# DSP.net
KiCad netlist of a schematic drawn in Altium Designer
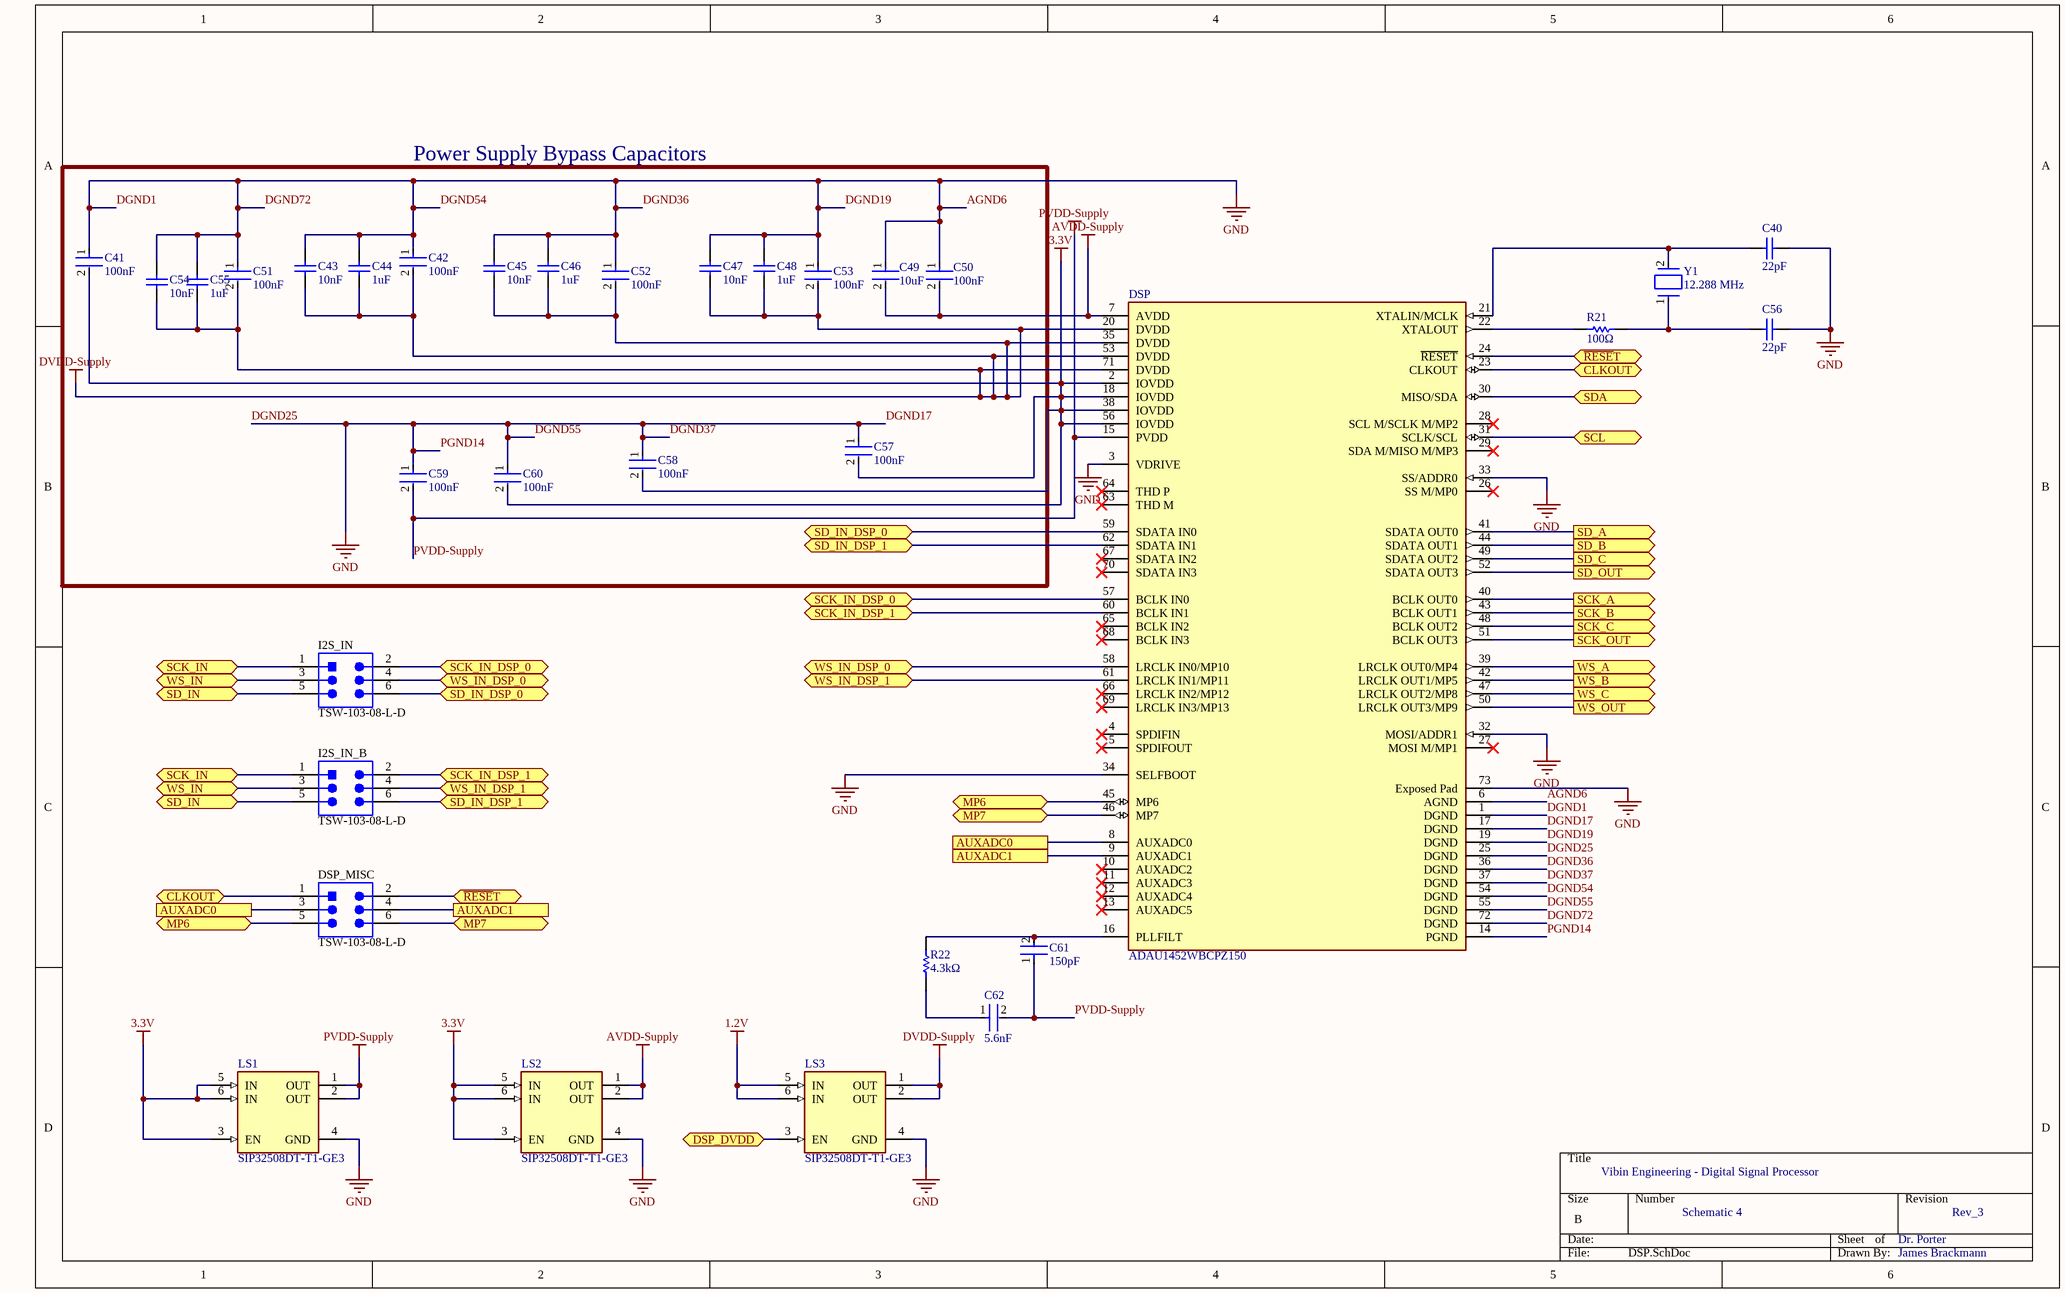
[diagram p0: DSP.SchDoc]

(export (version "E")
  (design (tool "Eeschema 10.0.6"))
  (components
    (comp (ref "C40")
      (value "22pF")
      (footprint "CAPC1608X90X35ML10T15")
      (fields (field (name "MANUFACTURER") "Murata"))
      (libsource (lib "Altium Content Vault") (part "CAP-NP-2"))
    )
    (comp (ref "C41")
      (value "100nF")
      (footprint "FP-C0402-BB-MFG")
      (description "CAP CER 0.1UF 10V X5R 0402             C0402C104K8PACTU")
      (fields (field (name "MANUFACTURER") "Kemet") (field (name "TOLERANCE") "0.1"))
      (libsource (lib "Altium Content Vault") (part "b4654b650e69147ec39a6b967a45e02"))
    )
    (comp (ref "C42")
      (value "100nF")
      (footprint "FP-C0402-BB-MFG")
      (description "CAP CER 0.1UF 10V X5R 0402             C0402C104K8PACTU")
      (fields (field (name "MANUFACTURER") "Kemet") (field (name "TOLERANCE") "0.1"))
      (libsource (lib "Altium Content Vault") (part "b4654b650e69147ec39a6b967a45e02"))
    )
    (comp (ref "C43")
      (value "10nF")
      (footprint "CAPC1005X56X25NL10T15")
      (description "0402ZC103KAT2A")
      (fields (field (name "MANUFACTURER") "AVX Interconnect / Elco"))
      (libsource (lib "Altium Content Vault") (part "CAP"))
    )
    (comp (ref "C44")
      (value "1uF")
      (footprint "CAPC2013X145X50LL20T25")
      (description "C0805C105K4PACTU")
      (fields (field (name "MANUFACTURER") "Kemet"))
      (libsource (lib "Altium Content Vault") (part "CAP"))
    )
    (comp (ref "C45")
      (value "10nF")
      (footprint "CAPC1005X56X25NL10T15")
      (description "0402ZC103KAT2A")
      (fields (field (name "MANUFACTURER") "AVX Interconnect / Elco"))
      (libsource (lib "Altium Content Vault") (part "CAP"))
    )
    (comp (ref "C46")
      (value "1uF")
      (footprint "CAPC2013X145X50LL20T25")
      (description "C0805C105K4PACTU")
      (fields (field (name "MANUFACTURER") "Kemet"))
      (libsource (lib "Altium Content Vault") (part "CAP"))
    )
    (comp (ref "C47")
      (value "10nF")
      (footprint "CAPC1005X56X25NL10T15")
      (description "0402ZC103KAT2A")
      (fields (field (name "MANUFACTURER") "AVX Interconnect / Elco"))
      (libsource (lib "Altium Content Vault") (part "CAP"))
    )
    (comp (ref "C48")
      (value "1uF")
      (footprint "CAPC2013X145X50LL20T25")
      (description "C0805C105K4PACTU")
      (fields (field (name "MANUFACTURER") "Kemet"))
      (libsource (lib "Altium Content Vault") (part "CAP"))
    )
    (comp (ref "C49")
      (value "10uF")
      (footprint "FP-GRM188-0_1-e0_2_0_55-IPC_A")
      (fields (field (name "VOLTAGE") "6.3V") (field (name "TOLERANCE") "20%"))
      (libsource (lib "Altium Content Vault") (part "02cd4be3c70576c341d710602a673aa"))
    )
    (comp (ref "C50")
      (value "100nF")
      (footprint "FP-C0402-BB-MFG")
      (description "CAP CER 0.1UF 10V X5R 0402             C0402C104K8PACTU")
      (fields (field (name "MANUFACTURER") "Kemet") (field (name "TOLERANCE") "0.1"))
      (libsource (lib "Altium Content Vault") (part "b4654b650e69147ec39a6b967a45e02"))
    )
    (comp (ref "C51")
      (value "100nF")
      (footprint "FP-C0402-BB-MFG")
      (description "CAP CER 0.1UF 10V X5R 0402             C0402C104K8PACTU")
      (fields (field (name "MANUFACTURER") "Kemet") (field (name "TOLERANCE") "0.1"))
      (libsource (lib "Altium Content Vault") (part "b4654b650e69147ec39a6b967a45e02"))
    )
    (comp (ref "C52")
      (value "100nF")
      (footprint "FP-C0402-BB-MFG")
      (description "CAP CER 0.1UF 10V X5R 0402             C0402C104K8PACTU")
      (fields (field (name "MANUFACTURER") "Kemet") (field (name "TOLERANCE") "0.1"))
      (libsource (lib "Altium Content Vault") (part "b4654b650e69147ec39a6b967a45e02"))
    )
    (comp (ref "C53")
      (value "100nF")
      (footprint "FP-C0402-BB-MFG")
      (description "CAP CER 0.1UF 10V X5R 0402             C0402C104K8PACTU")
      (fields (field (name "MANUFACTURER") "Kemet") (field (name "TOLERANCE") "0.1"))
      (libsource (lib "Altium Content Vault") (part "b4654b650e69147ec39a6b967a45e02"))
    )
    (comp (ref "C54")
      (value "10nF")
      (footprint "CAPC1005X56X25NL10T15")
      (description "0402ZC103KAT2A")
      (fields (field (name "MANUFACTURER") "AVX Interconnect / Elco"))
      (libsource (lib "Altium Content Vault") (part "CAP"))
    )
    (comp (ref "C55")
      (value "1uF")
      (footprint "CAPC2013X145X50LL20T25")
      (description "C0805C105K4PACTU")
      (fields (field (name "MANUFACTURER") "Kemet"))
      (libsource (lib "Altium Content Vault") (part "CAP"))
    )
    (comp (ref "C56")
      (value "22pF")
      (footprint "CAPC1608X90X35ML10T15")
      (fields (field (name "MANUFACTURER") "Murata"))
      (libsource (lib "Altium Content Vault") (part "CAP-NP-2"))
    )
    (comp (ref "C57")
      (value "100nF")
      (footprint "FP-C0402-BB-MFG")
      (description "CAP CER 0.1UF 10V X5R 0402             C0402C104K8PACTU")
      (fields (field (name "MANUFACTURER") "Kemet") (field (name "TOLERANCE") "0.1"))
      (libsource (lib "Altium Content Vault") (part "b4654b650e69147ec39a6b967a45e02"))
    )
    (comp (ref "C58")
      (value "100nF")
      (footprint "FP-C0402-BB-MFG")
      (description "CAP CER 0.1UF 10V X5R 0402             C0402C104K8PACTU")
      (fields (field (name "MANUFACTURER") "Kemet") (field (name "TOLERANCE") "0.1"))
      (libsource (lib "Altium Content Vault") (part "b4654b650e69147ec39a6b967a45e02"))
    )
    (comp (ref "C59")
      (value "100nF")
      (footprint "FP-C0402-BB-MFG")
      (description "CAP CER 0.1UF 10V X5R 0402             C0402C104K8PACTU")
      (fields (field (name "MANUFACTURER") "Kemet") (field (name "TOLERANCE") "0.1"))
      (libsource (lib "Altium Content Vault") (part "b4654b650e69147ec39a6b967a45e02"))
    )
    (comp (ref "C60")
      (value "100nF")
      (footprint "FP-C0402-BB-MFG")
      (description "CAP CER 0.1UF 10V X5R 0402             C0402C104K8PACTU")
      (fields (field (name "MANUFACTURER") "Kemet") (field (name "TOLERANCE") "0.1"))
      (libsource (lib "Altium Content Vault") (part "b4654b650e69147ec39a6b967a45e02"))
    )
    (comp (ref "C61")
      (value "150pF")
      (footprint "FP-0805-L_2_01_0_2-W_1_25-IPC_B")
      (description "General Purpose Ceramic Capacitor, 0805, 150pF, 5%, C0G, 30ppm/°C, 200V         08052A151JAT2A")
      (fields (field (name "TOLERANCE") "5%") (field (name "VOLTAGE") "200V"))
      (libsource (lib "Altium Content Vault") (part "02cd4be3c70576c341d710602a673aa"))
    )
    (comp (ref "C62")
      (value "5.6nF")
      (footprint "FP-CL10-IPC_A")
      (description "Cap Ceramic 5.6nF 50V X7R ±10% Pad SMD 0603 +125°C T/R            CL10B562KB8NNNC")
      (fields (field (name "VOLTAGE") "50V") (field (name "TOLERANCE") "10%"))
      (libsource (lib "Altium Content Vault") (part "b4654b650e69147ec39a6b967a45e02"))
    )
    (comp (ref "DSP")
      (value "ADAU1452WBCPZ150")
      (footprint "FP-CP-72-6-IPC_B")
      (description "150 MHZ 32BIT SIGMADSP AUDIO PRO")
      (fields (field (name "MANUFACTURER") "Analog Devices"))
      (libsource (lib "VibinTest1_1") (part "CMP-09089-000039-1"))
    )
    (comp (ref "DSP_MISC")
      (value "TSW-103-08-L-D")
      (footprint "SMTC-TSW-103-08-L-D_V")
      (fields (field (name "MANUFACTURER") "Samtec"))
      (libsource (lib "Altium Content Vault") (part "CN-2P-M-R6"))
    )
    (comp (ref "I2S_IN")
      (value "TSW-103-08-L-D")
      (footprint "SMTC-TSW-103-08-L-D_V")
      (fields (field (name "MANUFACTURER") "Samtec"))
      (libsource (lib "Altium Content Vault") (part "CN-2P-M-R6"))
    )
    (comp (ref "I2S_IN_B")
      (value "TSW-103-08-L-D")
      (footprint "SMTC-TSW-103-08-L-D_V")
      (fields (field (name "MANUFACTURER") "Samtec"))
      (libsource (lib "Altium Content Vault") (part "CN-2P-M-R6"))
    )
    (comp (ref "LS1")
      (value "SIP32508DT-T1-GE3")
      (footprint "FP-E13-1126-IPC_C")
      (description "IC PWR SWTCH N-CHAN 1:1 TSOT23-6")
      (fields
        (field (name "OCTOPART") "https://octopart.com/sip32508dt-t1-ge3-vishay-29622757")
        (field (name "MANUFACTURER") "Vishay")
      )
      (libsource (lib "Altium Content Vault") (part "141890209d49669e58eba095c1ea2ce"))
    )
    (comp (ref "LS2")
      (value "SIP32508DT-T1-GE3")
      (footprint "FP-E13-1126-IPC_C")
      (description "IC PWR SWTCH N-CHAN 1:1 TSOT23-6")
      (fields
        (field (name "OCTOPART") "https://octopart.com/sip32508dt-t1-ge3-vishay-29622757")
        (field (name "MANUFACTURER") "Vishay")
      )
      (libsource (lib "Altium Content Vault") (part "141890209d49669e58eba095c1ea2ce"))
    )
    (comp (ref "LS3")
      (value "SIP32508DT-T1-GE3")
      (footprint "FP-E13-1126-IPC_C")
      (description "IC PWR SWTCH N-CHAN 1:1 TSOT23-6")
      (fields
        (field (name "OCTOPART") "https://octopart.com/sip32508dt-t1-ge3-vishay-29622757")
        (field (name "MANUFACTURER") "Vishay")
      )
      (libsource (lib "Altium Content Vault") (part "141890209d49669e58eba095c1ea2ce"))
    )
    (comp (ref "R21")
      (value "100Ω")
      (footprint "RESC2013X60X40ML20T25")
      (description "ERA6AEB101V")
      (fields (field (name "MANUFACTURER") "Panasonic"))
      (libsource (lib "Altium Content Vault") (part "RES"))
    )
    (comp (ref "R22")
      (value "4.3kΩ")
      (footprint "RESC1005X40X25ML05T10")
      (description "RC0402FR-074K3L")
      (fields (field (name "MANUFACTURER") "Yageo / Phycomp"))
      (libsource (lib "Altium Content Vault") (part "RES"))
    )
    (comp (ref "Y1")
      (value "12.288 MHz")
      (footprint "FP-ABM3-MFG")
      (description "Crystal 12.288MHz ±20ppm 18pF SMD-2 5mm x 3.2mm           ABM3-12.288MHZ-D2Y-T")
      (fields (field (name "TOLERANCE") "20ppm"))
      (libsource (lib "Altium Content Vault") (part "c23a69dc6c9e2f18f2079038eb95dd1"))
    )
  )
  (nets
    (net (code "1") (name "/AUXADC0") (class "Default")
      (node (ref "DSP") (pin "8") (pinfunction "AUXADC0_8") (pintype "passive"))
      (node (ref "DSP_MISC") (pin "3") (pinfunction "3_3") (pintype "passive"))
    )
    (net (code "2") (name "/AUXADC1") (class "Default")
      (node (ref "DSP") (pin "9") (pinfunction "AUXADC1_9") (pintype "passive"))
      (node (ref "DSP_MISC") (pin "4") (pinfunction "4_4") (pintype "passive"))
    )
    (net (code "3") (name "/CLKOUT") (class "Default")
      (node (ref "DSP") (pin "23") (pinfunction "CLKOUT_23") (pintype "bidirectional"))
      (node (ref "DSP_MISC") (pin "1") (pinfunction "1_1") (pintype "passive"))
    )
    (net (code "4") (name "/DSP_DVDD") (class "Default")
      (node (ref "LS3") (pin "3") (pinfunction "EN_3") (pintype "input"))
    )
    (net (code "5") (name "/MP6") (class "Default")
      (node (ref "DSP") (pin "45") (pinfunction "MP6_45") (pintype "bidirectional"))
      (node (ref "DSP_MISC") (pin "5") (pinfunction "5_5") (pintype "passive"))
    )
    (net (code "6") (name "/MP7") (class "Default")
      (node (ref "DSP") (pin "46") (pinfunction "MP7_46") (pintype "bidirectional"))
      (node (ref "DSP_MISC") (pin "6") (pinfunction "6_6") (pintype "passive"))
    )
    (net (code "7") (name "/SCK_A") (class "Default")
      (node (ref "DSP") (pin "40") (pinfunction "BCLK_OUT0_40") (pintype "output"))
    )
    (net (code "8") (name "/SCK_B") (class "Default")
      (node (ref "DSP") (pin "43") (pinfunction "BCLK_OUT1_43") (pintype "output"))
    )
    (net (code "9") (name "/SCK_C") (class "Default")
      (node (ref "DSP") (pin "48") (pinfunction "BCLK_OUT2_48") (pintype "output"))
    )
    (net (code "10") (name "/SCK_IN") (class "Default")
      (node (ref "I2S_IN") (pin "1") (pinfunction "1_1") (pintype "passive"))
      (node (ref "I2S_IN_B") (pin "1") (pinfunction "1_1") (pintype "passive"))
    )
    (net (code "11") (name "/SCK_IN_DSP_0") (class "Default")
      (node (ref "DSP") (pin "57") (pinfunction "BCLK_IN0_57") (pintype "passive"))
      (node (ref "I2S_IN") (pin "2") (pinfunction "2_2") (pintype "passive"))
    )
    (net (code "12") (name "/SCK_IN_DSP_1") (class "Default")
      (node (ref "DSP") (pin "60") (pinfunction "BCLK_IN1_60") (pintype "passive"))
      (node (ref "I2S_IN_B") (pin "2") (pinfunction "2_2") (pintype "passive"))
    )
    (net (code "13") (name "/SCK_OUT") (class "Default")
      (node (ref "DSP") (pin "51") (pinfunction "BCLK_OUT3_51") (pintype "output"))
    )
    (net (code "14") (name "/SCL") (class "Default")
      (node (ref "DSP") (pin "31") (pinfunction "SCLK/SCL_31") (pintype "bidirectional"))
    )
    (net (code "15") (name "/SDA") (class "Default")
      (node (ref "DSP") (pin "30") (pinfunction "MISO/SDA_30") (pintype "bidirectional"))
    )
    (net (code "16") (name "/SD_A") (class "Default")
      (node (ref "DSP") (pin "41") (pinfunction "SDATA_OUT0_41") (pintype "output"))
    )
    (net (code "17") (name "/SD_B") (class "Default")
      (node (ref "DSP") (pin "44") (pinfunction "SDATA_OUT1_44") (pintype "output"))
    )
    (net (code "18") (name "/SD_C") (class "Default")
      (node (ref "DSP") (pin "49") (pinfunction "SDATA_OUT2_49") (pintype "output"))
    )
    (net (code "19") (name "/SD_IN") (class "Default")
      (node (ref "I2S_IN") (pin "5") (pinfunction "5_5") (pintype "passive"))
      (node (ref "I2S_IN_B") (pin "5") (pinfunction "5_5") (pintype "passive"))
    )
    (net (code "20") (name "/SD_IN_DSP_0") (class "Default")
      (node (ref "DSP") (pin "59") (pinfunction "SDATA_IN0_59") (pintype "passive"))
      (node (ref "I2S_IN") (pin "6") (pinfunction "6_6") (pintype "passive"))
    )
    (net (code "21") (name "/SD_IN_DSP_1") (class "Default")
      (node (ref "DSP") (pin "62") (pinfunction "SDATA_IN1_62") (pintype "passive"))
      (node (ref "I2S_IN_B") (pin "6") (pinfunction "6_6") (pintype "passive"))
    )
    (net (code "22") (name "/SD_OUT") (class "Default")
      (node (ref "DSP") (pin "52") (pinfunction "SDATA_OUT3_52") (pintype "output"))
    )
    (net (code "23") (name "/WS_A") (class "Default")
      (node (ref "DSP") (pin "39") (pinfunction "LRCLK_OUT0/MP4_39") (pintype "output"))
    )
    (net (code "24") (name "/WS_B") (class "Default")
      (node (ref "DSP") (pin "42") (pinfunction "LRCLK_OUT1/MP5_42") (pintype "output"))
    )
    (net (code "25") (name "/WS_C") (class "Default")
      (node (ref "DSP") (pin "47") (pinfunction "LRCLK_OUT2/MP8_47") (pintype "output"))
    )
    (net (code "26") (name "/WS_IN") (class "Default")
      (node (ref "I2S_IN") (pin "3") (pinfunction "3_3") (pintype "passive"))
      (node (ref "I2S_IN_B") (pin "3") (pinfunction "3_3") (pintype "passive"))
    )
    (net (code "27") (name "/WS_IN_DSP_0") (class "Default")
      (node (ref "DSP") (pin "58") (pinfunction "LRCLK_IN0/MP10_58") (pintype "passive"))
      (node (ref "I2S_IN") (pin "4") (pinfunction "4_4") (pintype "passive"))
    )
    (net (code "28") (name "/WS_IN_DSP_1") (class "Default")
      (node (ref "DSP") (pin "61") (pinfunction "LRCLK_IN1/MP11_61") (pintype "passive"))
      (node (ref "I2S_IN_B") (pin "4") (pinfunction "4_4") (pintype "passive"))
    )
    (net (code "29") (name "/WS_OUT") (class "Default")
      (node (ref "DSP") (pin "50") (pinfunction "LRCLK_OUT3/MP9_50") (pintype "output"))
    )
    (net (code "30") (name "/~{RESE}T") (class "Default")
      (node (ref "DSP") (pin "24") (pinfunction "~{RESET}_24") (pintype "input"))
      (node (ref "DSP_MISC") (pin "2") (pinfunction "2_2") (pintype "passive"))
    )
    (net (code "31") (name "1.2V") (class "Default")
      (node (ref "LS3") (pin "5") (pinfunction "IN_5") (pintype "input"))
      (node (ref "LS3") (pin "6") (pinfunction "IN_6") (pintype "input"))
    )
    (net (code "32") (name "3.3V") (class "Default")
      (node (ref "C41") (pin "2") (pinfunction "2_2") (pintype "passive"))
      (node (ref "C57") (pin "2") (pinfunction "2_2") (pintype "passive"))
      (node (ref "C58") (pin "2") (pinfunction "2_2") (pintype "passive"))
      (node (ref "C60") (pin "2") (pinfunction "2_2") (pintype "passive"))
      (node (ref "DSP") (pin "18") (pinfunction "IOVDD_18") (pintype "power_in"))
      (node (ref "DSP") (pin "2") (pinfunction "IOVDD_2") (pintype "power_in"))
      (node (ref "DSP") (pin "38") (pinfunction "IOVDD_38") (pintype "power_in"))
      (node (ref "DSP") (pin "56") (pinfunction "IOVDD_56") (pintype "power_in"))
      (node (ref "LS1") (pin "3") (pinfunction "EN_3") (pintype "input"))
      (node (ref "LS1") (pin "5") (pinfunction "IN_5") (pintype "input"))
      (node (ref "LS1") (pin "6") (pinfunction "IN_6") (pintype "input"))
      (node (ref "LS2") (pin "3") (pinfunction "EN_3") (pintype "input"))
      (node (ref "LS2") (pin "5") (pinfunction "IN_5") (pintype "input"))
      (node (ref "LS2") (pin "6") (pinfunction "IN_6") (pintype "input"))
    )
    (net (code "33") (name "AVDD-Supply") (class "Default")
      (node (ref "C49") (pin "2") (pinfunction "2_2") (pintype "passive"))
      (node (ref "C50") (pin "2") (pinfunction "2_2") (pintype "passive"))
      (node (ref "DSP") (pin "7") (pinfunction "AVDD_7") (pintype "power_in"))
      (node (ref "LS2") (pin "1") (pinfunction "OUT_1") (pintype "passive"))
      (node (ref "LS2") (pin "2") (pinfunction "OUT_2") (pintype "passive"))
    )
    (net (code "34") (name "DVDD-Supply") (class "Default")
      (node (ref "C42") (pin "2") (pinfunction "2_2") (pintype "passive"))
      (node (ref "C43") (pin "1") (pinfunction "1_1") (pintype "passive"))
      (node (ref "C44") (pin "1") (pinfunction "1_1") (pintype "passive"))
      (node (ref "C45") (pin "1") (pinfunction "1_1") (pintype "passive"))
      (node (ref "C46") (pin "1") (pinfunction "1_1") (pintype "passive"))
      (node (ref "C47") (pin "1") (pinfunction "1_1") (pintype "passive"))
      (node (ref "C48") (pin "1") (pinfunction "1_1") (pintype "passive"))
      (node (ref "C51") (pin "2") (pinfunction "2_2") (pintype "passive"))
      (node (ref "C52") (pin "2") (pinfunction "2_2") (pintype "passive"))
      (node (ref "C53") (pin "2") (pinfunction "2_2") (pintype "passive"))
      (node (ref "C54") (pin "1") (pinfunction "1_1") (pintype "passive"))
      (node (ref "C55") (pin "1") (pinfunction "1_1") (pintype "passive"))
      (node (ref "DSP") (pin "20") (pinfunction "DVDD_20") (pintype "power_in"))
      (node (ref "DSP") (pin "35") (pinfunction "DVDD_35") (pintype "power_in"))
      (node (ref "DSP") (pin "53") (pinfunction "DVDD_53") (pintype "power_in"))
      (node (ref "DSP") (pin "71") (pinfunction "DVDD_71") (pintype "power_in"))
      (node (ref "LS3") (pin "1") (pinfunction "OUT_1") (pintype "passive"))
      (node (ref "LS3") (pin "2") (pinfunction "OUT_2") (pintype "passive"))
    )
    (net (code "35") (name "GND") (class "Default")
      (node (ref "C40") (pin "2") (pinfunction "2_2") (pintype "passive"))
      (node (ref "C41") (pin "1") (pinfunction "1_1") (pintype "passive"))
      (node (ref "C42") (pin "1") (pinfunction "1_1") (pintype "passive"))
      (node (ref "C43") (pin "2") (pinfunction "2_2") (pintype "passive"))
      (node (ref "C44") (pin "2") (pinfunction "2_2") (pintype "passive"))
      (node (ref "C45") (pin "2") (pinfunction "2_2") (pintype "passive"))
      (node (ref "C46") (pin "2") (pinfunction "2_2") (pintype "passive"))
      (node (ref "C47") (pin "2") (pinfunction "2_2") (pintype "passive"))
      (node (ref "C48") (pin "2") (pinfunction "2_2") (pintype "passive"))
      (node (ref "C49") (pin "1") (pinfunction "1_1") (pintype "passive"))
      (node (ref "C50") (pin "1") (pinfunction "1_1") (pintype "passive"))
      (node (ref "C51") (pin "1") (pinfunction "1_1") (pintype "passive"))
      (node (ref "C52") (pin "1") (pinfunction "1_1") (pintype "passive"))
      (node (ref "C53") (pin "1") (pinfunction "1_1") (pintype "passive"))
      (node (ref "C54") (pin "2") (pinfunction "2_2") (pintype "passive"))
      (node (ref "C55") (pin "2") (pinfunction "2_2") (pintype "passive"))
      (node (ref "C56") (pin "2") (pinfunction "2_2") (pintype "passive"))
      (node (ref "C57") (pin "1") (pinfunction "1_1") (pintype "passive"))
      (node (ref "C58") (pin "1") (pinfunction "1_1") (pintype "passive"))
      (node (ref "C59") (pin "1") (pinfunction "1_1") (pintype "passive"))
      (node (ref "C60") (pin "1") (pinfunction "1_1") (pintype "passive"))
      (node (ref "DSP") (pin "1") (pinfunction "DGND_1") (pintype "power_in"))
      (node (ref "DSP") (pin "14") (pinfunction "PGND_14") (pintype "power_in"))
      (node (ref "DSP") (pin "17") (pinfunction "DGND_17") (pintype "power_in"))
      (node (ref "DSP") (pin "19") (pinfunction "DGND_19") (pintype "power_in"))
      (node (ref "DSP") (pin "25") (pinfunction "DGND_25") (pintype "power_in"))
      (node (ref "DSP") (pin "3") (pinfunction "VDRIVE_3") (pintype "passive"))
      (node (ref "DSP") (pin "32") (pinfunction "MOSI/ADDR1_32") (pintype "input"))
      (node (ref "DSP") (pin "33") (pinfunction "SS/ADDR0_33") (pintype "input"))
      (node (ref "DSP") (pin "34") (pinfunction "SELFBOOT_34") (pintype "passive"))
      (node (ref "DSP") (pin "36") (pinfunction "DGND_36") (pintype "power_in"))
      (node (ref "DSP") (pin "37") (pinfunction "DGND_37") (pintype "power_in"))
      (node (ref "DSP") (pin "54") (pinfunction "DGND_54") (pintype "power_in"))
      (node (ref "DSP") (pin "55") (pinfunction "DGND_55") (pintype "power_in"))
      (node (ref "DSP") (pin "6") (pinfunction "AGND_6") (pintype "power_in"))
      (node (ref "DSP") (pin "72") (pinfunction "DGND_72") (pintype "power_in"))
      (node (ref "DSP") (pin "73") (pinfunction "Exposed_Pad_73") (pintype "power_in"))
      (node (ref "LS1") (pin "4") (pinfunction "GND_4") (pintype "power_in"))
      (node (ref "LS2") (pin "4") (pinfunction "GND_4") (pintype "power_in"))
      (node (ref "LS3") (pin "4") (pinfunction "GND_4") (pintype "power_in"))
    )
    (net (code "36") (name "Net-(C56-Pad1)") (class "Default")
      (node (ref "C56") (pin "1") (pinfunction "1_1") (pintype "passive"))
      (node (ref "R21") (pin "2") (pinfunction "2_2") (pintype "passive"))
      (node (ref "Y1") (pin "1") (pinfunction "1_1") (pintype "passive"))
    )
    (net (code "37") (name "Net-(C62-Pad1)") (class "Default")
      (node (ref "C62") (pin "1") (pinfunction "1_1") (pintype "passive"))
      (node (ref "R22") (pin "1") (pinfunction "1_1") (pintype "passive"))
    )
    (net (code "38") (name "Net-(DSP-PLLFILT)") (class "Default")
      (node (ref "C61") (pin "2") (pinfunction "2_2") (pintype "passive"))
      (node (ref "DSP") (pin "16") (pinfunction "PLLFILT_16") (pintype "passive"))
      (node (ref "R22") (pin "2") (pinfunction "2_2") (pintype "passive"))
    )
    (net (code "39") (name "Net-(DSP-XTALIN{slash}MCLK)") (class "Default")
      (node (ref "C40") (pin "1") (pinfunction "1_1") (pintype "passive"))
      (node (ref "DSP") (pin "21") (pinfunction "XTALIN/MCLK_21") (pintype "input"))
      (node (ref "Y1") (pin "2") (pinfunction "2_2") (pintype "passive"))
    )
    (net (code "40") (name "Net-(DSP-XTALOUT)") (class "Default")
      (node (ref "DSP") (pin "22") (pinfunction "XTALOUT_22") (pintype "output"))
      (node (ref "R21") (pin "1") (pinfunction "1_1") (pintype "passive"))
    )
    (net (code "41") (name "PVDD-Supply") (class "Default")
      (node (ref "C59") (pin "2") (pinfunction "2_2") (pintype "passive"))
      (node (ref "C61") (pin "1") (pinfunction "1_1") (pintype "passive"))
      (node (ref "C62") (pin "2") (pinfunction "2_2") (pintype "passive"))
      (node (ref "DSP") (pin "15") (pinfunction "PVDD_15") (pintype "power_in"))
      (node (ref "LS1") (pin "1") (pinfunction "OUT_1") (pintype "passive"))
      (node (ref "LS1") (pin "2") (pinfunction "OUT_2") (pintype "passive"))
    )
    (net (code "42") (name "unconnected-(DSP-AUXADC2-Pad10)") (class "Default")
      (node (ref "DSP") (pin "10") (pinfunction "AUXADC2_10") (pintype "passive+no_connect"))
    )
    (net (code "43") (name "unconnected-(DSP-AUXADC3-Pad11)") (class "Default")
      (node (ref "DSP") (pin "11") (pinfunction "AUXADC3_11") (pintype "passive+no_connect"))
    )
    (net (code "44") (name "unconnected-(DSP-AUXADC4-Pad12)") (class "Default")
      (node (ref "DSP") (pin "12") (pinfunction "AUXADC4_12") (pintype "passive+no_connect"))
    )
    (net (code "45") (name "unconnected-(DSP-AUXADC5-Pad13)") (class "Default")
      (node (ref "DSP") (pin "13") (pinfunction "AUXADC5_13") (pintype "passive+no_connect"))
    )
    (net (code "46") (name "unconnected-(DSP-BCLK_IN2-Pad65)") (class "Default")
      (node (ref "DSP") (pin "65") (pinfunction "BCLK_IN2_65") (pintype "passive+no_connect"))
    )
    (net (code "47") (name "unconnected-(DSP-BCLK_IN3-Pad68)") (class "Default")
      (node (ref "DSP") (pin "68") (pinfunction "BCLK_IN3_68") (pintype "passive+no_connect"))
    )
    (net (code "48") (name "unconnected-(DSP-LRCLK_IN2{slash}MP12-Pad66)") (class "Default")
      (node (ref "DSP") (pin "66") (pinfunction "LRCLK_IN2/MP12_66") (pintype "passive+no_connect"))
    )
    (net (code "49") (name "unconnected-(DSP-LRCLK_IN3{slash}MP13-Pad69)") (class "Default")
      (node (ref "DSP") (pin "69") (pinfunction "LRCLK_IN3/MP13_69") (pintype "passive+no_connect"))
    )
    (net (code "50") (name "unconnected-(DSP-MOSI_M{slash}MP1-Pad27)") (class "Default")
      (node (ref "DSP") (pin "27") (pinfunction "MOSI_M/MP1_27") (pintype "passive+no_connect"))
    )
    (net (code "51") (name "unconnected-(DSP-SCL_M{slash}SCLK_M{slash}MP2-Pad28)") (class "Default")
      (node (ref "DSP") (pin "28") (pinfunction "SCL_M/SCLK_M/MP2_28") (pintype "passive+no_connect"))
    )
    (net (code "52") (name "unconnected-(DSP-SDATA_IN2-Pad67)") (class "Default")
      (node (ref "DSP") (pin "67") (pinfunction "SDATA_IN2_67") (pintype "passive+no_connect"))
    )
    (net (code "53") (name "unconnected-(DSP-SDATA_IN3-Pad70)") (class "Default")
      (node (ref "DSP") (pin "70") (pinfunction "SDATA_IN3_70") (pintype "passive+no_connect"))
    )
    (net (code "54") (name "unconnected-(DSP-SDA_M{slash}MISO_M{slash}MP3-Pad29)") (class "Default")
      (node (ref "DSP") (pin "29") (pinfunction "SDA_M/MISO_M/MP3_29") (pintype "passive+no_connect"))
    )
    (net (code "55") (name "unconnected-(DSP-SPDIFIN-Pad4)") (class "Default")
      (node (ref "DSP") (pin "4") (pinfunction "SPDIFIN_4") (pintype "passive+no_connect"))
    )
    (net (code "56") (name "unconnected-(DSP-SPDIFOUT-Pad5)") (class "Default")
      (node (ref "DSP") (pin "5") (pinfunction "SPDIFOUT_5") (pintype "passive+no_connect"))
    )
    (net (code "57") (name "unconnected-(DSP-SS_M{slash}MP0-Pad26)") (class "Default")
      (node (ref "DSP") (pin "26") (pinfunction "SS_M/MP0_26") (pintype "passive+no_connect"))
    )
    (net (code "58") (name "unconnected-(DSP-THD_M-Pad63)") (class "Default")
      (node (ref "DSP") (pin "63") (pinfunction "THD_M_63") (pintype "passive+no_connect"))
    )
    (net (code "59") (name "unconnected-(DSP-THD_P-Pad64)") (class "Default")
      (node (ref "DSP") (pin "64") (pinfunction "THD_P_64") (pintype "passive+no_connect"))
    )
  )
)
